# 12-multimodal-accelerometer.net
KiCad netlist of a schematic drawn in Altium Designer
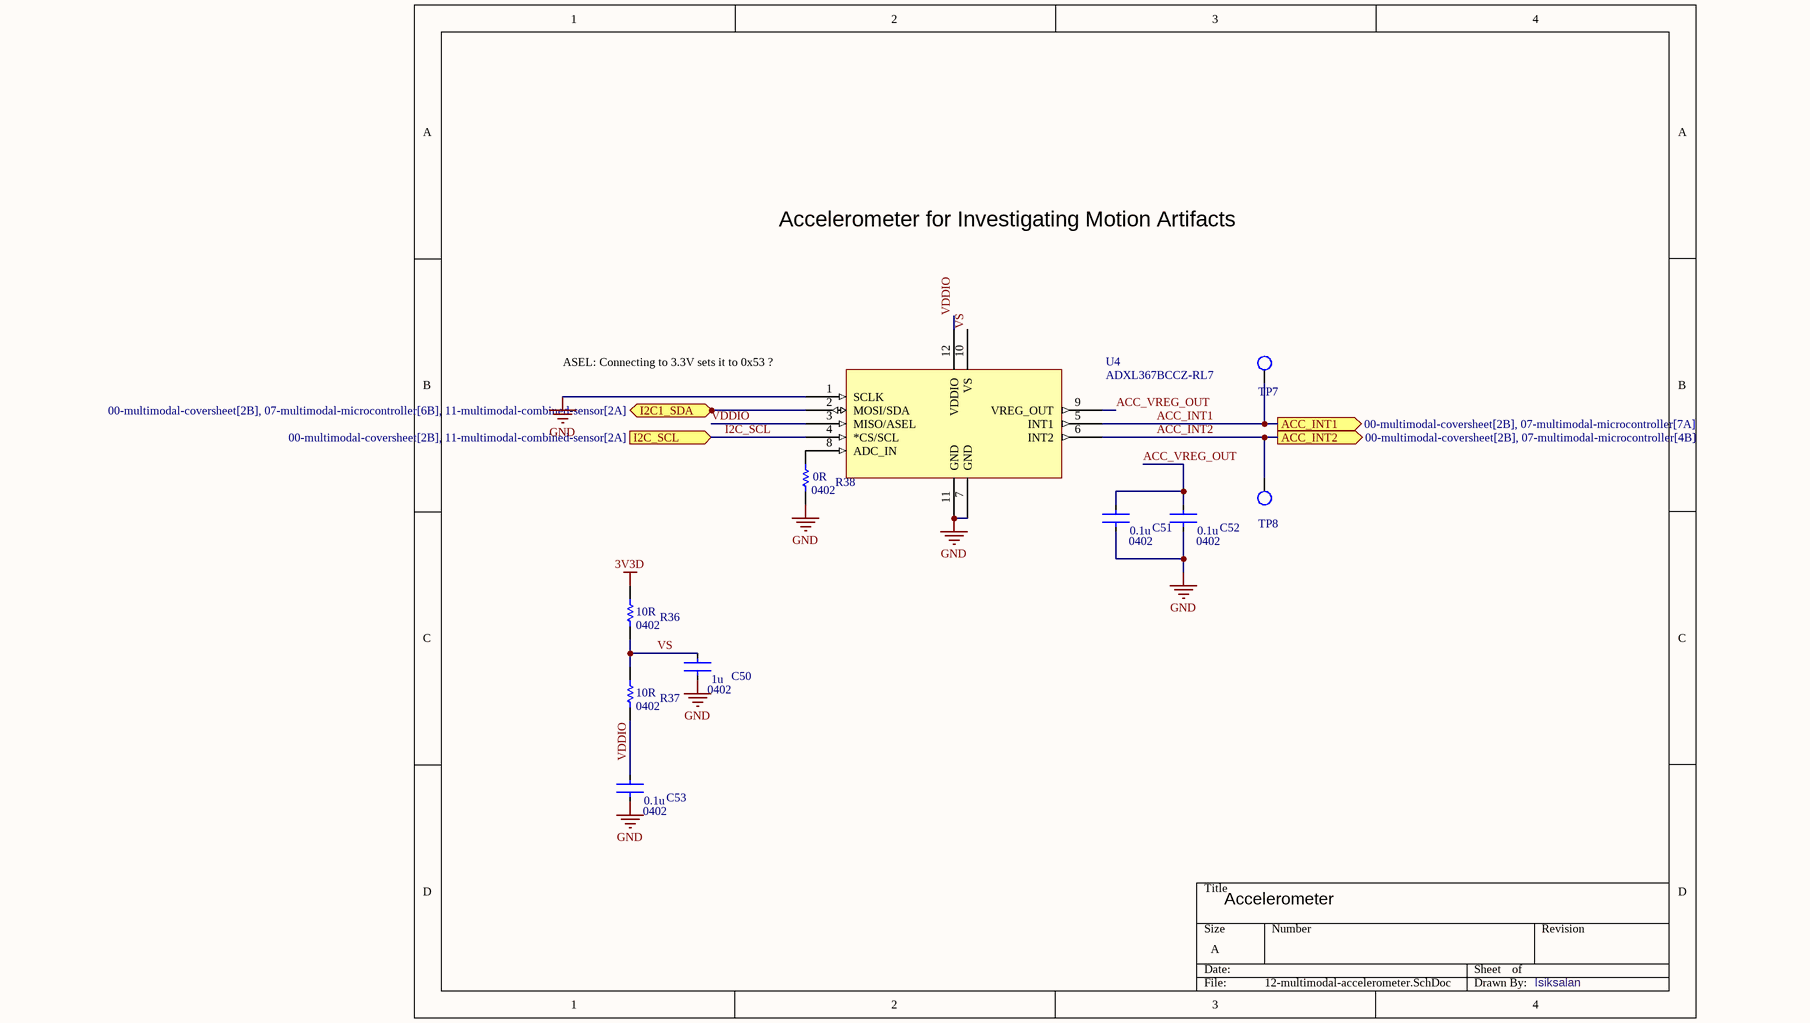
[diagram p0: 12-multimodal-accelerometer.SchDoc]

(export (version "E")
  (design (tool "Eeschema 10.0.6"))
  (components
    (comp (ref "C50")
      (value "C1005X5R1V105K050BC")
      (footprint "CAPTDK0402")
      (description "CAP CER 1UF 35V X5R 0402")
      (libsource (lib "multimodal") (part "C1005X5R1V105K050BC"))
    )
    (comp (ref "C51")
      (value "C1005X7R1H104K050BB")
      (footprint "CAPTDK0402")
      (description "CAP CER 0.1UF 50V X7R 0402")
      (libsource (lib "multimodal") (part "C1005X7R1H104K050BB"))
    )
    (comp (ref "C52")
      (value "C1005X7R1H104K050BB")
      (footprint "CAPTDK0402")
      (description "CAP CER 0.1UF 50V X7R 0402")
      (libsource (lib "multimodal") (part "C1005X7R1H104K050BB"))
    )
    (comp (ref "C53")
      (value "C1005X7R1H104K050BB")
      (footprint "CAPTDK0402")
      (description "CAP CER 0.1UF 50V X7R 0402")
      (libsource (lib "multimodal") (part "C1005X7R1H104K050BB"))
    )
    (comp (ref "R36")
      (value "RMCF0402FT10R0")
      (footprint "RES-STACK-POLE-0402")
      (description "RES 10 OHM 1% 1/16W 0402")
      (libsource (lib "multimodal") (part "RMCF0402FT10R0"))
    )
    (comp (ref "R37")
      (value "RMCF0402FT10R0")
      (footprint "RES-STACK-POLE-0402")
      (description "RES 10 OHM 1% 1/16W 0402")
      (libsource (lib "multimodal") (part "RMCF0402FT10R0"))
    )
    (comp (ref "R38")
      (value "RMCF0402ZT0R00")
      (footprint "RES-STACK-POLE-0402")
      (description "RES 0 OHM JUMPER 1/16W 0402")
      (libsource (lib "multimodal") (part "RMCF0402ZT0R00"))
    )
    (comp (ref "TP7")
      (value "TESTPOINT_S")
      (footprint "TESTPOINT_S")
      (description "Testpoint Surface Pad")
      (libsource (lib "multimodal") (part "TESTPOINT_S"))
    )
    (comp (ref "TP8")
      (value "TESTPOINT_S")
      (footprint "TESTPOINT_S")
      (description "Testpoint Surface Pad")
      (libsource (lib "multimodal") (part "TESTPOINT_S"))
    )
    (comp (ref "U4")
      (value "ADXL367BCCZ-RL7")
      (footprint "ADXL367BCCZ-RL7")
      (description "Accelerometer X, Y, Z Axis ±2g, 4g, 8g 6.25Hz ~ 200Hz 12-LGA (2.2x2.3)")
      (fields (field (name "COPYRIGHT") "Copyright (C) 2025 Ultra Librarian. All rights reserved."))
      (libsource (lib "multimodal") (part "ADXL367BCCZ-RL7"))
    )
  )
  (nets
    (net (code "1") (name "/ACC_INT1") (class "Default")
      (node (ref "TP7") (pin "1") (pinfunction "1_1") (pintype "passive"))
      (node (ref "U4") (pin "5") (pinfunction "INT1_5") (pintype "output"))
    )
    (net (code "2") (name "/ACC_INT2") (class "Default")
      (node (ref "TP8") (pin "1") (pinfunction "1_1") (pintype "passive"))
      (node (ref "U4") (pin "6") (pinfunction "INT2_6") (pintype "output"))
    )
    (net (code "3") (name "/ACC_VREG_OUT") (class "Default")
      (node (ref "C51") (pin "1") (pinfunction "1_1") (pintype "passive"))
      (node (ref "C52") (pin "1") (pinfunction "1_1") (pintype "passive"))
      (node (ref "U4") (pin "9") (pinfunction "VREG_OUT_9") (pintype "output"))
    )
    (net (code "4") (name "/I2C1_SDA") (class "Default")
      (node (ref "U4") (pin "2") (pinfunction "MOSI/SDA_2") (pintype "bidirectional"))
    )
    (net (code "5") (name "/I2C_SCL") (class "Default")
      (node (ref "U4") (pin "4") (pinfunction "*CS/SCL_4") (pintype "input"))
    )
    (net (code "6") (name "/VDDIO") (class "Default")
      (node (ref "C53") (pin "1") (pinfunction "1_1") (pintype "passive"))
      (node (ref "R37") (pin "1") (pinfunction "1_1") (pintype "passive"))
      (node (ref "U4") (pin "12") (pinfunction "VDDIO_12") (pintype "power_in"))
      (node (ref "U4") (pin "3") (pinfunction "MISO/ASEL_3") (pintype "input"))
    )
    (net (code "7") (name "/VS") (class "Default")
      (node (ref "C50") (pin "1") (pinfunction "1_1") (pintype "passive"))
      (node (ref "R36") (pin "1") (pinfunction "1_1") (pintype "passive"))
      (node (ref "R37") (pin "2") (pinfunction "2_2") (pintype "passive"))
      (node (ref "U4") (pin "10") (pinfunction "VS_10") (pintype "power_in"))
    )
    (net (code "8") (name "3V3D") (class "Default")
      (node (ref "R36") (pin "2") (pinfunction "2_2") (pintype "passive"))
    )
    (net (code "9") (name "GND") (class "Default")
      (node (ref "C50") (pin "2") (pinfunction "2_2") (pintype "passive"))
      (node (ref "C51") (pin "2") (pinfunction "2_2") (pintype "passive"))
      (node (ref "C52") (pin "2") (pinfunction "2_2") (pintype "passive"))
      (node (ref "C53") (pin "2") (pinfunction "2_2") (pintype "passive"))
      (node (ref "R38") (pin "1") (pinfunction "1_1") (pintype "passive"))
      (node (ref "U4") (pin "1") (pinfunction "SCLK_1") (pintype "input"))
      (node (ref "U4") (pin "11") (pinfunction "GND_11") (pintype "power_in"))
      (node (ref "U4") (pin "7") (pinfunction "GND_7") (pintype "power_in"))
    )
    (net (code "10") (name "Net-(U4-ADC_IN)") (class "Default")
      (node (ref "R38") (pin "2") (pinfunction "2_2") (pintype "passive"))
      (node (ref "U4") (pin "8") (pinfunction "ADC_IN_8") (pintype "input"))
    )
  )
)
